# Opamp.net
KiCad netlist of a schematic drawn in Altium Designer
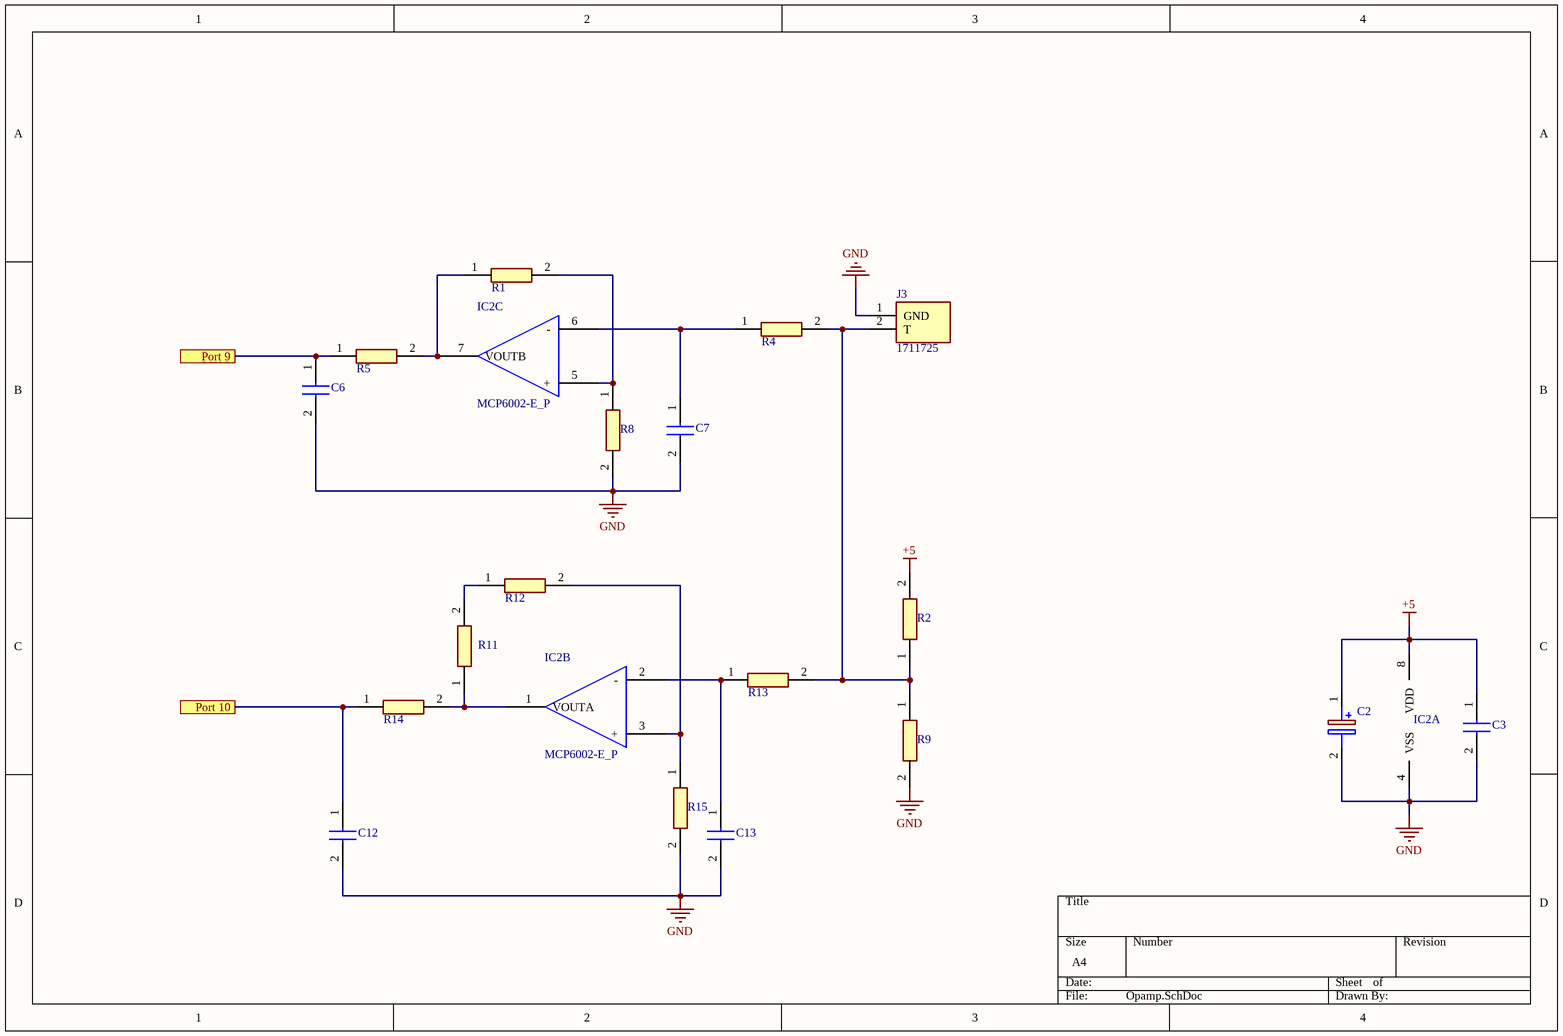
[diagram p0: Opamp.SchDoc]

(export (version "E")
  (design (tool "Eeschema 10.0.6"))
  (components
    (comp (ref "C2")
      (value "EEU-FR1H100")
      (footprint "10µF 50V")
      (description "Capacitor Polarised 50VDC 10uF")
      (fields (field (name "MOUSER2 PART NUMBER") "667-EEU-FR1H100"))
      (libsource (lib "Schlib1") (part "EEU-FR1H100"))
    )
    (comp (ref "C3")
      (value "C0805C104K5RAC7411")
      (footprint "100nF")
      (description "Capacitor  0.1 uF 50VDC")
      (fields (field (name "MOUSER2 PART NUMBER") "80-C0805C104K5RACLR"))
      (libsource (lib "Schlib1") (part "C0805C104K5RAC7411"))
    )
    (comp (ref "C6")
      (value "C0805C103K5TACAUTO")
      (footprint "10nF")
      (description "Capacitor 0.01µF 50VDC")
      (libsource (lib "Schlib1") (part "C0805C103K5TACAUTO"))
    )
    (comp (ref "C7")
      (value "C0805C103K5TACAUTO")
      (footprint "10nF")
      (description "Capacitor 0.01µF 50VDC")
      (libsource (lib "Schlib1") (part "C0805C103K5TACAUTO"))
    )
    (comp (ref "C12")
      (value "C0805C103K5TACAUTO")
      (footprint "10nF")
      (description "Capacitor 0.01µF 50VDC")
      (libsource (lib "Schlib1") (part "C0805C103K5TACAUTO"))
    )
    (comp (ref "C13")
      (value "C0805C103K5TACAUTO")
      (footprint "10nF")
      (description "Capacitor 0.01µF 50VDC")
      (libsource (lib "Schlib1") (part "C0805C103K5TACAUTO"))
    )
    (comp (ref "IC2")
      (value "MCP6002-E_P")
      (footprint "DIP781W56P254L950H533Q8N")
      (description "Integrated Circuit, opamp")
      (fields
        (field (name "MOUSER2 PART NUMBER") "579-MCP6002-E/P")
        (field (name "MANUFACTURER_PART_NUMBER") "MCP6002-E/P")
      )
      (libsource (lib "Schlib1") (part "MCP6002-E_P"))
    )
    (comp (ref "J3")
      (value "1711725")
      (footprint "1711725")
      (description "Connector")
      (libsource (lib "Schlib1") (part "1711725"))
    )
    (comp (ref "R1")
      (value "CRCW080510K0DHEAP")
      (footprint "Resistor")
      (description "Resistor 10KOhm")
      (libsource (lib "") (part "CRCW080510K0DHEAP_1"))
    )
    (comp (ref "R2")
      (value "CR0805-JW-105ELF")
      (footprint "Resistor")
      (description "Resistor 1MOhm")
      (libsource (lib "Schlib1") (part "CR0805-JW-105ELF"))
    )
    (comp (ref "R4")
      (value "CRCW08055K60FKTA")
      (footprint "Resistor")
      (description "Resistor 5.6KOhm")
      (libsource (lib "Schlib1") (part "CRCW08055K60FKTA"))
    )
    (comp (ref "R5")
      (value "CRCW08055K60FKTA")
      (footprint "Resistor")
      (description "Resistor 5.6KOhm")
      (libsource (lib "Schlib1") (part "CRCW08055K60FKTA"))
    )
    (comp (ref "R8")
      (value "CPF0805B18KE")
      (footprint "Resistor")
      (description "Resistor 510Ohm")
      (libsource (lib "Schlib1") (part "CPF0805B18KE"))
    )
    (comp (ref "R9")
      (value "CR0805-JW-105ELF")
      (footprint "Resistor")
      (description "Resistor 1MOhm")
      (libsource (lib "") (part "CR0805-JW-105ELF_1"))
    )
    (comp (ref "R11")
      (value "CRCW080510K0DHEAP")
      (footprint "Resistor")
      (description "Resistor 10KOhm")
      (libsource (lib "Schlib1") (part "CRCW080510K0DHEAP"))
    )
    (comp (ref "R12")
      (value "CRCW080510K0DHEAP")
      (footprint "Resistor")
      (description "Resistor 10KOhm")
      (libsource (lib "") (part "CRCW080510K0DHEAP_1"))
    )
    (comp (ref "R13")
      (value "CRCW08055K60FKTA")
      (footprint "Resistor")
      (description "Resistor 5.6KOhm")
      (libsource (lib "Schlib1") (part "CRCW08055K60FKTA"))
    )
    (comp (ref "R14")
      (value "CRCW08055K60FKTA")
      (footprint "Resistor")
      (description "Resistor 5.6KOhm")
      (libsource (lib "Schlib1") (part "CRCW08055K60FKTA"))
    )
    (comp (ref "R15")
      (value "CPF0805B18KE")
      (footprint "Resistor")
      (description "Resistor 510Ohm")
      (libsource (lib "Schlib1") (part "CPF0805B18KE"))
    )
  )
  (nets
    (net (code "1") (name "+5") (class "Default")
      (node (ref "C2") (pin "1") (pinfunction "+_1") (pintype "power_in"))
      (node (ref "C3") (pin "1") (pinfunction "1_1") (pintype "passive"))
      (node (ref "IC2") (pin "8") (pinfunction "VDD_8") (pintype "passive"))
      (node (ref "R2") (pin "2") (pinfunction "2_2") (pintype "passive"))
    )
    (net (code "2") (name "/Port 9") (class "Default")
      (node (ref "C6") (pin "1") (pinfunction "1_1") (pintype "passive"))
      (node (ref "R5") (pin "1") (pinfunction "1_1") (pintype "passive"))
    )
    (net (code "3") (name "/Port 10") (class "Default")
      (node (ref "C12") (pin "1") (pinfunction "1_1") (pintype "passive"))
      (node (ref "R14") (pin "1") (pinfunction "1_1") (pintype "passive"))
    )
    (net (code "4") (name "GND") (class "Default")
      (node (ref "C12") (pin "2") (pinfunction "2_2") (pintype "passive"))
      (node (ref "C13") (pin "2") (pinfunction "2_2") (pintype "passive"))
      (node (ref "C2") (pin "2") (pinfunction "-_2") (pintype "power_in"))
      (node (ref "C3") (pin "2") (pinfunction "2_2") (pintype "passive"))
      (node (ref "C6") (pin "2") (pinfunction "2_2") (pintype "passive"))
      (node (ref "C7") (pin "2") (pinfunction "2_2") (pintype "passive"))
      (node (ref "IC2") (pin "4") (pinfunction "VSS_4") (pintype "passive"))
      (node (ref "J3") (pin "1") (pinfunction "GND_1") (pintype "passive"))
      (node (ref "R15") (pin "2") (pinfunction "2_2") (pintype "passive"))
      (node (ref "R8") (pin "2") (pinfunction "2_2") (pintype "passive"))
      (node (ref "R9") (pin "2") (pinfunction "2_2") (pintype "passive"))
    )
    (net (code "5") (name "Net-(IC2B-+)") (class "Default")
      (node (ref "IC2") (pin "3") (pinfunction "+_3") (pintype "passive"))
      (node (ref "R12") (pin "2") (pinfunction "2_2") (pintype "passive"))
      (node (ref "R15") (pin "1") (pinfunction "1_1") (pintype "passive"))
    )
    (net (code "6") (name "Net-(IC2B--)") (class "Default")
      (node (ref "C13") (pin "1") (pinfunction "1_1") (pintype "passive"))
      (node (ref "IC2") (pin "2") (pinfunction "-_2") (pintype "passive"))
      (node (ref "R13") (pin "1") (pinfunction "1_1") (pintype "passive"))
    )
    (net (code "7") (name "Net-(IC2B-VOUTA)") (class "Default")
      (node (ref "IC2") (pin "1") (pinfunction "VOUTA_1") (pintype "passive"))
      (node (ref "R11") (pin "1") (pinfunction "1_1") (pintype "passive"))
      (node (ref "R14") (pin "2") (pinfunction "2_2") (pintype "passive"))
    )
    (net (code "8") (name "Net-(IC2C-+)") (class "Default")
      (node (ref "IC2") (pin "5") (pinfunction "+_5") (pintype "passive"))
      (node (ref "R1") (pin "2") (pinfunction "2_2") (pintype "passive"))
      (node (ref "R8") (pin "1") (pinfunction "1_1") (pintype "passive"))
    )
    (net (code "9") (name "Net-(IC2C--)") (class "Default")
      (node (ref "C7") (pin "1") (pinfunction "1_1") (pintype "passive"))
      (node (ref "IC2") (pin "6") (pinfunction "-_6") (pintype "passive"))
      (node (ref "R4") (pin "1") (pinfunction "1_1") (pintype "passive"))
    )
    (net (code "10") (name "Net-(IC2C-VOUTB)") (class "Default")
      (node (ref "IC2") (pin "7") (pinfunction "VOUTB_7") (pintype "passive"))
      (node (ref "R1") (pin "1") (pinfunction "1_1") (pintype "passive"))
      (node (ref "R5") (pin "2") (pinfunction "2_2") (pintype "passive"))
    )
    (net (code "11") (name "Net-(J3-T)") (class "Default")
      (node (ref "J3") (pin "2") (pinfunction "T_2") (pintype "passive"))
      (node (ref "R13") (pin "2") (pinfunction "2_2") (pintype "passive"))
      (node (ref "R2") (pin "1") (pinfunction "1_1") (pintype "passive"))
      (node (ref "R4") (pin "2") (pinfunction "2_2") (pintype "passive"))
      (node (ref "R9") (pin "1") (pinfunction "1_1") (pintype "passive"))
    )
    (net (code "12") (name "Net-(R11-Pad2)") (class "Default")
      (node (ref "R11") (pin "2") (pinfunction "2_2") (pintype "passive"))
      (node (ref "R12") (pin "1") (pinfunction "1_1") (pintype "passive"))
    )
  )
)
